# SSTuino_Evo.net
KiCad netlist of a schematic drawn in EAGLE
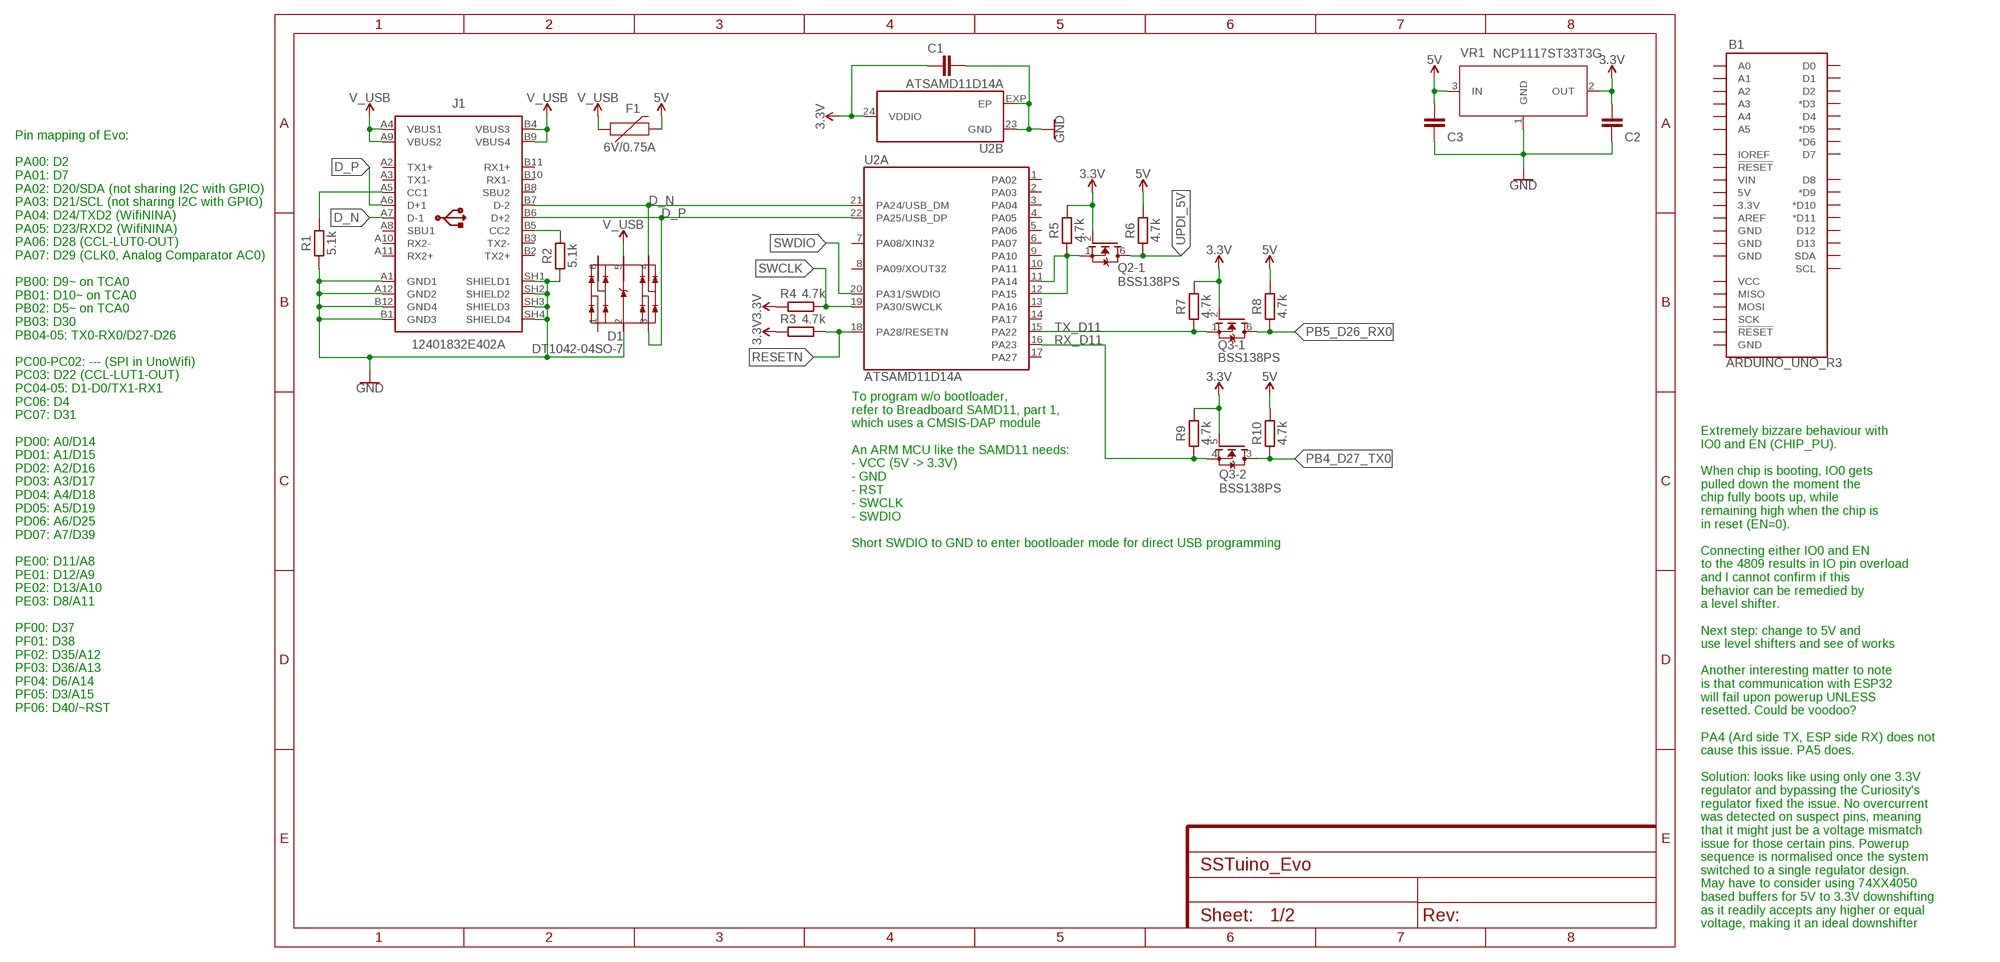
[diagram p0: schematic, sheet 1]
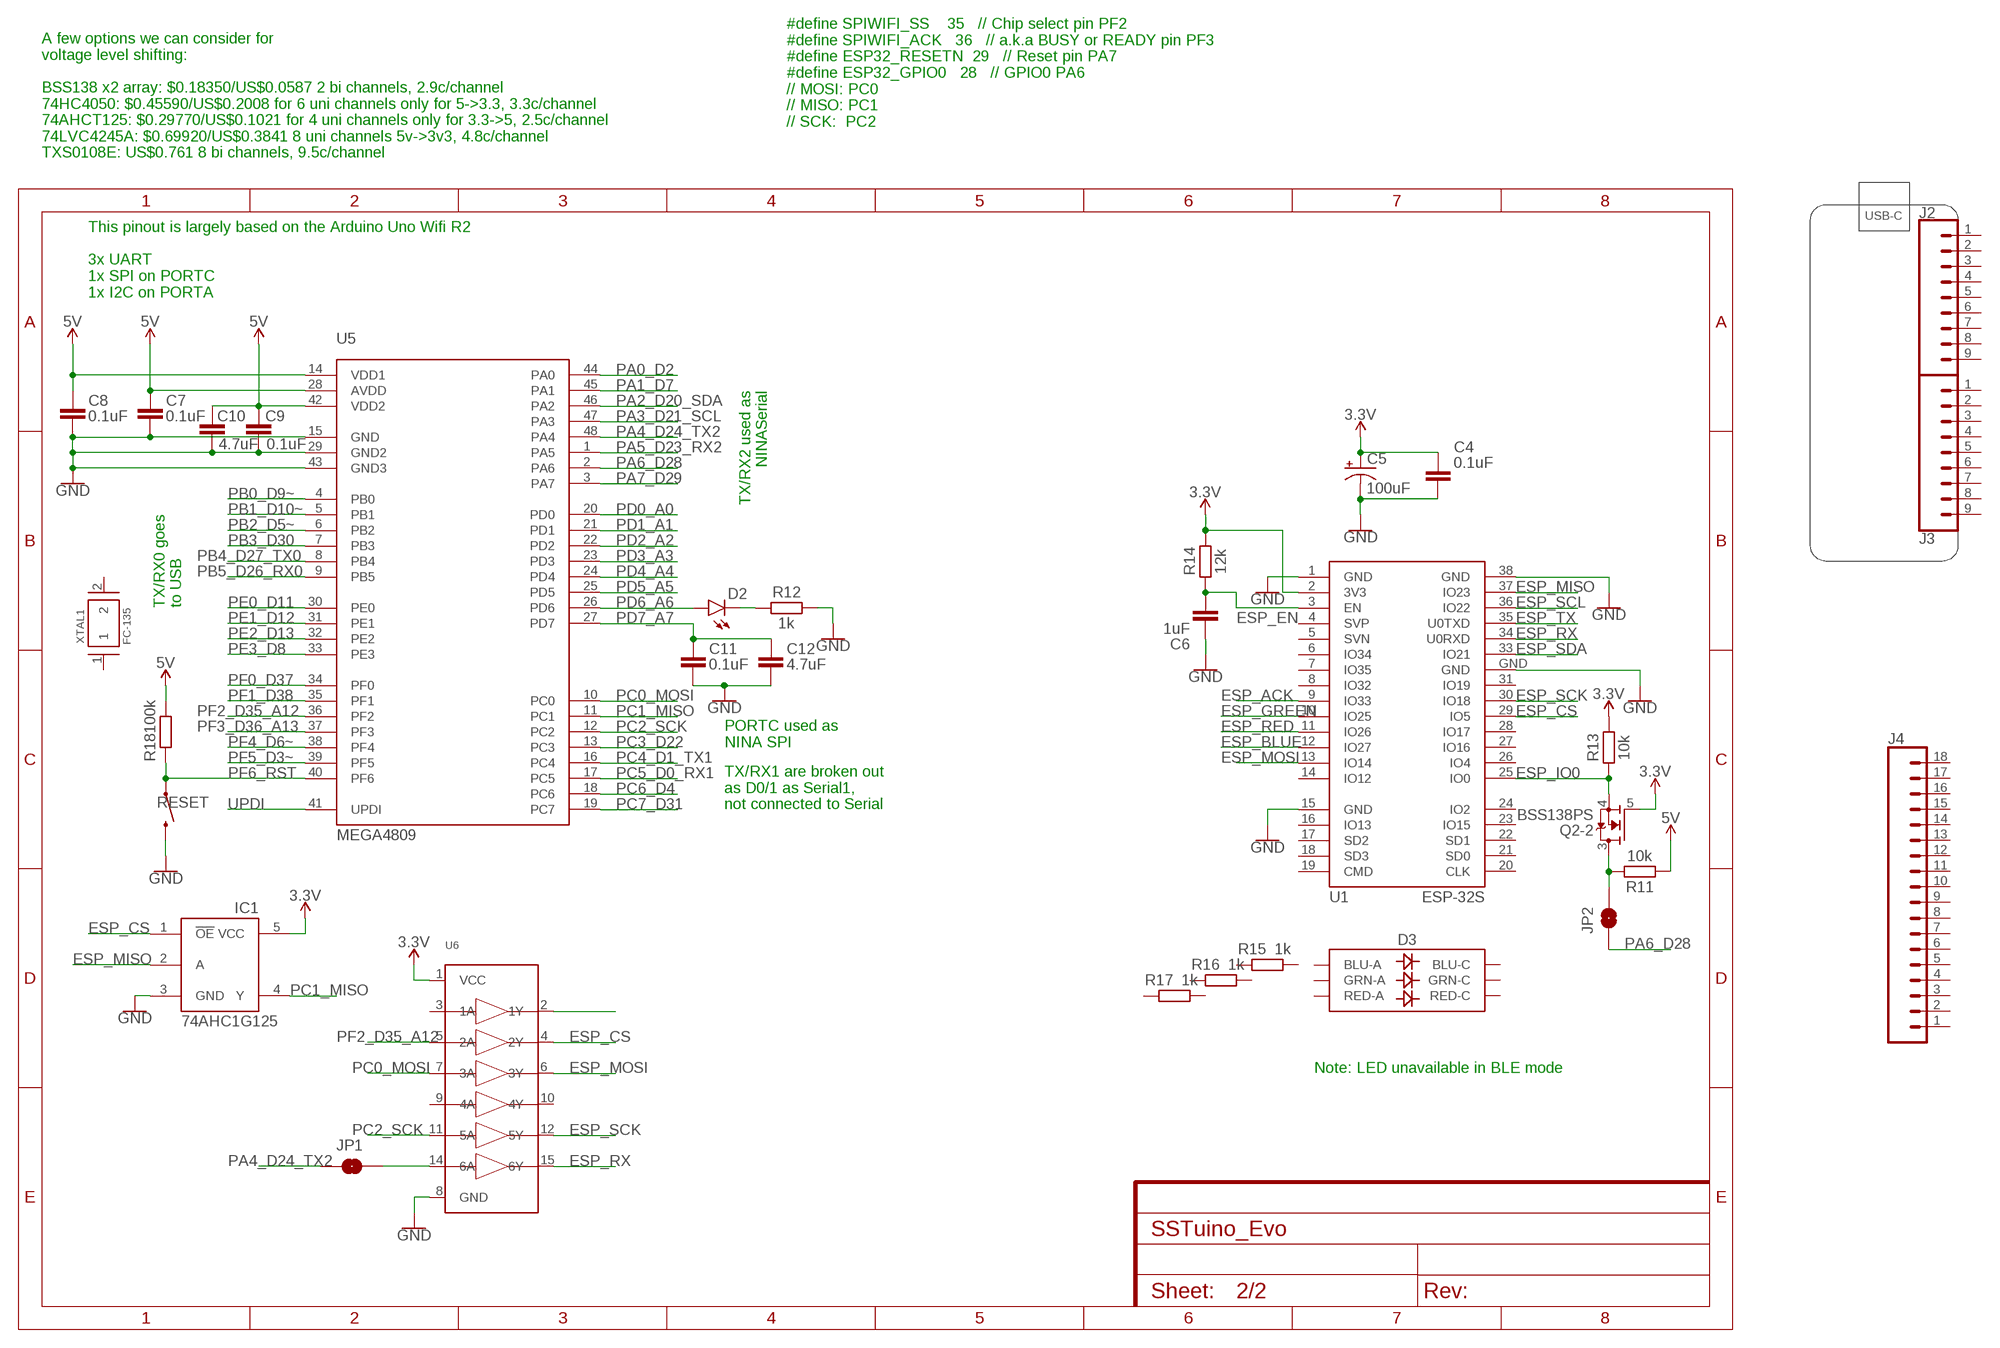
[diagram p1: schematic, sheet 2]

(export (version "E")
  (design (tool "Eeschema 10.0.6"))
  (components
    (comp (ref "B1")
      (value "ARDUINO_UNO_R3")
      (footprint "eagle-import:ARDUINO_R3")
      (libsource (lib "eagle-import") (part "ARDUINO_UNO_R3"))
    )
    (comp (ref "C1")
      (value "100n")
      (footprint "eagle-import:CAPC1005X60")
      (libsource (lib "eagle-import") (part "CCHIP-0402(1005-METRIC)_"))
    )
    (comp (ref "C2")
      (value "10uF")
      (footprint "eagle-import:CAPC1608X85")
      (libsource (lib "eagle-import") (part "CCHIP-0603(1608-METRIC)_"))
    )
    (comp (ref "C3")
      (value "10uF")
      (footprint "eagle-import:CAPC1608X85")
      (libsource (lib "eagle-import") (part "CCHIP-0603(1608-METRIC)_"))
    )
    (comp (ref "D1")
      (value "DT1042-04SO-7")
      (footprint "eagle-import:SOT95P285X140-6N")
      (fields (field (name "DIGI-KEY_PART_NUMBER") "DT1042-04SO-7DICT-ND") (field (name "MF") "Diodes Inc."))
      (libsource (lib "eagle-import") (part "DT1042-04SO-7"))
    )
    (comp (ref "F1")
      (value "6V/0.75A")
      (footprint "eagle-import:1206")
      (libsource (lib "eagle-import") (part "PPTC_THREE-QUARTER-AMP"))
    )
    (comp (ref "J1")
      (value "12401832E402A")
      (footprint "eagle-import:12401832E402A")
      (fields (field (name "MANUFACTURER") "Amphenol ICC"))
      (libsource (lib "eagle-import") (part "12401832E402A"))
    )
    (comp (ref "Q2")
      (value "BSS138PS")
      (footprint "eagle-import:ARDUINO-TRANSISTORS_SOT363")
      (fields (field (name "MANUFACTURER") "NXP"))
      (libsource (lib "eagle-import") (part "BSS138PS"))
    )
    (comp (ref "Q3")
      (value "BSS138PS")
      (footprint "eagle-import:ARDUINO-TRANSISTORS_SOT363")
      (fields (field (name "MANUFACTURER") "NXP"))
      (libsource (lib "eagle-import") (part "BSS138PS"))
    )
    (comp (ref "R1")
      (value "5.1k")
      (footprint "eagle-import:RESC1005X40")
      (libsource (lib "eagle-import") (part "RCHIP-0402(1005-METRIC)_"))
    )
    (comp (ref "R2")
      (value "5.1k")
      (footprint "eagle-import:RESC1005X40")
      (libsource (lib "eagle-import") (part "RCHIP-0402(1005-METRIC)_"))
    )
    (comp (ref "R3")
      (value "4.7k")
      (footprint "eagle-import:RESC1005X40")
      (libsource (lib "eagle-import") (part "RCHIP-0402(1005-METRIC)_"))
    )
    (comp (ref "R4")
      (value "4.7k")
      (footprint "eagle-import:RESC1005X40")
      (libsource (lib "eagle-import") (part "RCHIP-0402(1005-METRIC)_"))
    )
    (comp (ref "R5")
      (value "4.7k")
      (footprint "eagle-import:RESC1005X40")
      (libsource (lib "eagle-import") (part "RCHIP-0402(1005-METRIC)_"))
    )
    (comp (ref "R6")
      (value "4.7k")
      (footprint "eagle-import:RESC1005X40")
      (libsource (lib "eagle-import") (part "RCHIP-0402(1005-METRIC)_"))
    )
    (comp (ref "R7")
      (value "4.7k")
      (footprint "eagle-import:RESC1005X40")
      (libsource (lib "eagle-import") (part "RCHIP-0402(1005-METRIC)_"))
    )
    (comp (ref "R8")
      (value "4.7k")
      (footprint "eagle-import:RESC1005X40")
      (libsource (lib "eagle-import") (part "RCHIP-0402(1005-METRIC)_"))
    )
    (comp (ref "R9")
      (value "4.7k")
      (footprint "eagle-import:RESC1005X40")
      (libsource (lib "eagle-import") (part "RCHIP-0402(1005-METRIC)_"))
    )
    (comp (ref "R10")
      (value "4.7k")
      (footprint "eagle-import:RESC1005X40")
      (libsource (lib "eagle-import") (part "RCHIP-0402(1005-METRIC)_"))
    )
    (comp (ref "U2")
      (value "ATSAMD11D14A")
      (footprint "eagle-import:ARDUINO-UCS&SOCS_HVQFN24")
      (fields (field (name "MANUFACTURER") "Microchip"))
      (libsource (lib "eagle-import") (part "ATSAMD11D14"))
    )
    (comp (ref "VR1")
      (value "NCP1117ST33T3G")
      (footprint "eagle-import:SOT230P700X170-4")
      (fields (field (name "MANUFACTURER") "ON Semiconductor"))
      (libsource (lib "eagle-import") (part "NCP1117ST33T3GSOT-223"))
    )
    (comp (ref "C4")
      (value "0.1uF")
      (footprint "eagle-import:CAPC1005X60")
      (libsource (lib "eagle-import") (part "CCHIP-0402(1005-METRIC)_"))
    )
    (comp (ref "C5")
      (value "100uF")
      (footprint "eagle-import:CAPMP3216X180N")
      (libsource (lib "eagle-import") (part "C-POL-USTANTALUM-1206(3216-METRIC)_"))
    )
    (comp (ref "C6")
      (value "1uF")
      (footprint "eagle-import:CAPC1005X60")
      (libsource (lib "eagle-import") (part "CCHIP-0402(1005-METRIC)_"))
    )
    (comp (ref "C7")
      (value "0.1uF")
      (footprint "eagle-import:CAPC1005X60")
      (libsource (lib "eagle-import") (part "CCHIP-0402(1005-METRIC)_"))
    )
    (comp (ref "C8")
      (value "0.1uF")
      (footprint "eagle-import:CAPC1005X60")
      (libsource (lib "eagle-import") (part "CCHIP-0402(1005-METRIC)_"))
    )
    (comp (ref "C9")
      (value "0.1uF")
      (footprint "eagle-import:CAPC1005X60")
      (libsource (lib "eagle-import") (part "CCHIP-0402(1005-METRIC)_"))
    )
    (comp (ref "C10")
      (value "4.7uF")
      (footprint "eagle-import:CAPC1005X60")
      (libsource (lib "eagle-import") (part "CCHIP-0402(1005-METRIC)_"))
    )
    (comp (ref "C11")
      (value "0.1uF")
      (footprint "eagle-import:CAPC1005X60")
      (libsource (lib "eagle-import") (part "CCHIP-0402(1005-METRIC)_"))
    )
    (comp (ref "C12")
      (value "4.7uF")
      (footprint "eagle-import:CAPC1005X60")
      (libsource (lib "eagle-import") (part "CCHIP-0402(1005-METRIC)_"))
    )
    (comp (ref "D2")
      (value "LED0603")
      (footprint "eagle-import:LED-0603")
      (libsource (lib "eagle-import") (part "LED0603"))
    )
    (comp (ref "D3")
      (value "LED-RGBNO_IC")
      (footprint "eagle-import:LED-TRICOLOR-5050")
      (libsource (lib "eagle-import") (part "LED-RGBNO_IC"))
    )
    (comp (ref "IC1")
      (value "74AHC1G125")
      (footprint "eagle-import:SOT23-5L")
      (libsource (lib "eagle-import") (part "74AHC1G125"))
    )
    (comp (ref "J2")
      (value "CONN_09NO_SILK")
      (footprint "eagle-import:1X09_NO_SILK")
      (libsource (lib "eagle-import") (part "CONN_09NO_SILK"))
    )
    (comp (ref "J3")
      (value "CONN_09NO_SILK")
      (footprint "eagle-import:1X09_NO_SILK")
      (libsource (lib "eagle-import") (part "CONN_09NO_SILK"))
    )
    (comp (ref "J4")
      (value "CONN_18")
      (footprint "eagle-import:1X18")
      (libsource (lib "eagle-import") (part "CONN_18"))
    )
    (comp (ref "JP1")
      (value "JUMPER-SMT_2_NO_SILK")
      (footprint "eagle-import:SMT-JUMPER_2_NO_SILK")
      (libsource (lib "eagle-import") (part "JUMPER-SMT_2_NO_SILK"))
    )
    (comp (ref "JP2")
      (value "JUMPER-SMT_2_NO_SILK")
      (footprint "eagle-import:SMT-JUMPER_2_NO_SILK")
      (libsource (lib "eagle-import") (part "JUMPER-SMT_2_NO_SILK"))
    )
    (comp (ref "R11")
      (value "10k")
      (footprint "eagle-import:RESC1005X40")
      (libsource (lib "eagle-import") (part "RCHIP-0402(1005-METRIC)_"))
    )
    (comp (ref "R12")
      (value "1k")
      (footprint "eagle-import:RESC1005X40")
      (libsource (lib "eagle-import") (part "RCHIP-0402(1005-METRIC)_"))
    )
    (comp (ref "R13")
      (value "10k")
      (footprint "eagle-import:RESC1005X40")
      (libsource (lib "eagle-import") (part "RCHIP-0402(1005-METRIC)_"))
    )
    (comp (ref "R14")
      (value "12k")
      (footprint "eagle-import:RESC1005X40")
      (libsource (lib "eagle-import") (part "RCHIP-0402(1005-METRIC)_"))
    )
    (comp (ref "R15")
      (value "1k")
      (footprint "eagle-import:RESC1005X40")
      (libsource (lib "eagle-import") (part "RCHIP-0402(1005-METRIC)_"))
    )
    (comp (ref "R16")
      (value "1k")
      (footprint "eagle-import:RESC1005X40")
      (libsource (lib "eagle-import") (part "RCHIP-0402(1005-METRIC)_"))
    )
    (comp (ref "R17")
      (value "1k")
      (footprint "eagle-import:RESC1005X40")
      (libsource (lib "eagle-import") (part "RCHIP-0402(1005-METRIC)_"))
    )
    (comp (ref "R18")
      (value "100k")
      (footprint "eagle-import:RESC1005X40")
      (libsource (lib "eagle-import") (part "RCHIP-0402(1005-METRIC)_"))
    )
    (comp (ref "RESET")
      (value "MOMENTARY-SWITCH-SPST-SMD-4.6X2.8MM")
      (footprint "eagle-import:TACTILE_SWITCH_SMD_4.6X2.8MM")
      (libsource (lib "eagle-import") (part "MOMENTARY-SWITCH-SPST-SMD-4.6X2.8MM"))
    )
    (comp (ref "U1")
      (value "ESP-32S")
      (footprint "eagle-import:ESP-32S")
      (libsource (lib "eagle-import") (part "ESP-32S"))
    )
    (comp (ref "U5")
      (value "MEGA4809")
      (footprint "eagle-import:TQFP48")
      (libsource (lib "eagle-import") (part "MEGA4809"))
    )
    (comp (ref "U6")
      (value "74HC4050DTSSOP")
      (footprint "eagle-import:TSSOP16")
      (libsource (lib "eagle-import") (part "74HC4050DTSSOP"))
    )
    (comp (ref "XTAL1")
      (value "FC-135")
      (footprint "eagle-import:XTAL330X1051X90N")
      (fields (field (name "MANUFACTURER") "Seiko Epson Corporation"))
      (libsource (lib "eagle-import") (part "FC-135"))
    )
  )
  (nets
    (net (code "1") (name "3.3V") (class "Default")
      (node (ref "C1") (pin "1") (pinfunction "1_1") (pintype "passive"))
      (node (ref "C2") (pin "1") (pinfunction "1_1") (pintype "passive"))
      (node (ref "C4") (pin "1") (pinfunction "1_1") (pintype "passive"))
      (node (ref "C5") (pin "1") (pinfunction "+_1") (pintype "passive"))
      (node (ref "IC1") (pin "5") (pinfunction "VCC_5") (pintype "power_in"))
      (node (ref "Q2") (pin "2") (pinfunction "G_2") (pintype "passive"))
      (node (ref "Q2") (pin "5") (pinfunction "G_5") (pintype "passive"))
      (node (ref "Q3") (pin "2") (pinfunction "G_2") (pintype "passive"))
      (node (ref "Q3") (pin "5") (pinfunction "G_5") (pintype "passive"))
      (node (ref "R13") (pin "2") (pinfunction "2_2") (pintype "passive"))
      (node (ref "R14") (pin "2") (pinfunction "2_2") (pintype "passive"))
      (node (ref "R3") (pin "2") (pinfunction "2_2") (pintype "passive"))
      (node (ref "R4") (pin "2") (pinfunction "2_2") (pintype "passive"))
      (node (ref "R5") (pin "2") (pinfunction "2_2") (pintype "passive"))
      (node (ref "R7") (pin "2") (pinfunction "2_2") (pintype "passive"))
      (node (ref "R9") (pin "2") (pinfunction "2_2") (pintype "passive"))
      (node (ref "U1") (pin "2") (pinfunction "3V3_2") (pintype "power_in"))
      (node (ref "U2") (pin "24") (pinfunction "VDDIO_24") (pintype "power_in"))
      (node (ref "U6") (pin "1") (pinfunction "VCC_1") (pintype "bidirectional"))
      (node (ref "VR1") (pin "2") (pinfunction "OUT_2") (pintype "output"))
    )
    (net (code "2") (name "5V") (class "Default")
      (node (ref "C10") (pin "1") (pinfunction "1_1") (pintype "passive"))
      (node (ref "C3") (pin "1") (pinfunction "1_1") (pintype "passive"))
      (node (ref "C7") (pin "1") (pinfunction "1_1") (pintype "passive"))
      (node (ref "C8") (pin "1") (pinfunction "1_1") (pintype "passive"))
      (node (ref "C9") (pin "1") (pinfunction "1_1") (pintype "passive"))
      (node (ref "F1") (pin "2") (pinfunction "2_2") (pintype "bidirectional"))
      (node (ref "R10") (pin "2") (pinfunction "2_2") (pintype "passive"))
      (node (ref "R11") (pin "1") (pinfunction "1_1") (pintype "passive"))
      (node (ref "R18") (pin "2") (pinfunction "2_2") (pintype "passive"))
      (node (ref "R6") (pin "2") (pinfunction "2_2") (pintype "passive"))
      (node (ref "R8") (pin "2") (pinfunction "2_2") (pintype "passive"))
      (node (ref "U5") (pin "14") (pinfunction "VDD1_14") (pintype "bidirectional"))
      (node (ref "U5") (pin "28") (pinfunction "AVDD_28") (pintype "bidirectional"))
      (node (ref "U5") (pin "42") (pinfunction "VDD2_42") (pintype "bidirectional"))
      (node (ref "VR1") (pin "3") (pinfunction "IN_3") (pintype "input"))
    )
    (net (code "3") (name "D_N") (class "Default")
      (node (ref "D1") (pin "4") (pinfunction "IO3_4") (pintype "passive"))
      (node (ref "J1") (pin "A7") (pinfunction "D-1_A7") (pintype "bidirectional"))
      (node (ref "J1") (pin "B7") (pinfunction "D-2_B7") (pintype "bidirectional"))
      (node (ref "U2") (pin "21") (pinfunction "PA24/USB_DM_21") (pintype "bidirectional"))
    )
    (net (code "4") (name "D_P") (class "Default")
      (node (ref "D1") (pin "3") (pinfunction "IO2_3") (pintype "passive"))
      (node (ref "J1") (pin "A6") (pinfunction "D+1_A6") (pintype "bidirectional"))
      (node (ref "J1") (pin "B6") (pinfunction "D+2_B6") (pintype "bidirectional"))
      (node (ref "U2") (pin "22") (pinfunction "PA25/USB_DP_22") (pintype "bidirectional"))
    )
    (net (code "5") (name "ESP_ACK") (class "Default")
      (node (ref "U1") (pin "9") (pinfunction "IO33_9") (pintype "bidirectional"))
    )
    (net (code "6") (name "ESP_BLUE") (class "Default")
      (node (ref "U1") (pin "12") (pinfunction "IO27_12") (pintype "bidirectional"))
    )
    (net (code "7") (name "ESP_CS") (class "Default")
      (node (ref "IC1") (pin "1") (pinfunction "~{OE}_1") (pintype "input"))
      (node (ref "U1") (pin "29") (pinfunction "IO5_29") (pintype "bidirectional"))
      (node (ref "U6") (pin "4") (pinfunction "2Y_4") (pintype "bidirectional"))
    )
    (net (code "8") (name "ESP_EN") (class "Default")
      (node (ref "C6") (pin "2") (pinfunction "2_2") (pintype "passive"))
      (node (ref "R14") (pin "1") (pinfunction "1_1") (pintype "passive"))
      (node (ref "U1") (pin "3") (pinfunction "EN_3") (pintype "input"))
    )
    (net (code "9") (name "ESP_GREEN") (class "Default")
      (node (ref "U1") (pin "10") (pinfunction "IO25_10") (pintype "bidirectional"))
    )
    (net (code "10") (name "ESP_IO0") (class "Default")
      (node (ref "Q2") (pin "4") (pinfunction "S_4") (pintype "passive"))
      (node (ref "R13") (pin "1") (pinfunction "1_1") (pintype "passive"))
      (node (ref "U1") (pin "25") (pinfunction "IO0_25") (pintype "bidirectional"))
    )
    (net (code "11") (name "ESP_MISO") (class "Default")
      (node (ref "IC1") (pin "2") (pinfunction "A_2") (pintype "input"))
      (node (ref "U1") (pin "37") (pinfunction "IO23_37") (pintype "bidirectional"))
    )
    (net (code "12") (name "ESP_MOSI") (class "Default")
      (node (ref "U1") (pin "13") (pinfunction "IO14_13") (pintype "bidirectional"))
      (node (ref "U6") (pin "6") (pinfunction "3Y_6") (pintype "bidirectional"))
    )
    (net (code "13") (name "ESP_RED") (class "Default")
      (node (ref "U1") (pin "11") (pinfunction "IO26_11") (pintype "bidirectional"))
    )
    (net (code "14") (name "ESP_RX") (class "Default")
      (node (ref "U1") (pin "34") (pinfunction "U0RXD_34") (pintype "bidirectional"))
      (node (ref "U6") (pin "15") (pinfunction "6Y_15") (pintype "bidirectional"))
    )
    (net (code "15") (name "ESP_SCK") (class "Default")
      (node (ref "U1") (pin "30") (pinfunction "IO18_30") (pintype "bidirectional"))
      (node (ref "U6") (pin "12") (pinfunction "5Y_12") (pintype "bidirectional"))
    )
    (net (code "16") (name "ESP_SCL") (class "Default")
      (node (ref "U1") (pin "36") (pinfunction "IO22_36") (pintype "bidirectional"))
    )
    (net (code "17") (name "ESP_SDA") (class "Default")
      (node (ref "U1") (pin "33") (pinfunction "IO21_33") (pintype "bidirectional"))
    )
    (net (code "18") (name "ESP_TX") (class "Default")
      (node (ref "U1") (pin "35") (pinfunction "U0TXD_35") (pintype "bidirectional"))
    )
    (net (code "19") (name "GND") (class "Default")
      (node (ref "C1") (pin "2") (pinfunction "2_2") (pintype "passive"))
      (node (ref "C10") (pin "2") (pinfunction "2_2") (pintype "passive"))
      (node (ref "C11") (pin "2") (pinfunction "2_2") (pintype "passive"))
      (node (ref "C12") (pin "2") (pinfunction "2_2") (pintype "passive"))
      (node (ref "C2") (pin "2") (pinfunction "2_2") (pintype "passive"))
      (node (ref "C3") (pin "2") (pinfunction "2_2") (pintype "passive"))
      (node (ref "C4") (pin "2") (pinfunction "2_2") (pintype "passive"))
      (node (ref "C5") (pin "2") (pinfunction "-_2") (pintype "passive"))
      (node (ref "C6") (pin "1") (pinfunction "1_1") (pintype "passive"))
      (node (ref "C7") (pin "2") (pinfunction "2_2") (pintype "passive"))
      (node (ref "C8") (pin "2") (pinfunction "2_2") (pintype "passive"))
      (node (ref "C9") (pin "2") (pinfunction "2_2") (pintype "passive"))
      (node (ref "D1") (pin "2") (pinfunction "VSS_2") (pintype "power_in"))
      (node (ref "IC1") (pin "3") (pinfunction "GND_3") (pintype "power_in"))
      (node (ref "J1") (pin "A1") (pinfunction "GND1_A1") (pintype "power_in"))
      (node (ref "J1") (pin "A12") (pinfunction "GND2_A12") (pintype "power_in"))
      (node (ref "J1") (pin "B1") (pinfunction "GND3_B1") (pintype "power_in"))
      (node (ref "J1") (pin "B12") (pinfunction "GND4_B12") (pintype "power_in"))
      (node (ref "J1") (pin "SH1") (pinfunction "SHIELD1_SH1") (pintype "power_in"))
      (node (ref "J1") (pin "SH2") (pinfunction "SHIELD2_SH2") (pintype "power_in"))
      (node (ref "J1") (pin "SH3") (pinfunction "SHIELD3_SH3") (pintype "power_in"))
      (node (ref "J1") (pin "SH4") (pinfunction "SHIELD4_SH4") (pintype "power_in"))
      (node (ref "R1") (pin "1") (pinfunction "1_1") (pintype "passive"))
      (node (ref "R12") (pin "2") (pinfunction "2_2") (pintype "passive"))
      (node (ref "R2") (pin "1") (pinfunction "1_1") (pintype "passive"))
      (node (ref "RESET") (pin "3") (pinfunction "2_3") (pintype "passive"))
      (node (ref "RESET") (pin "4") (pinfunction "2_4") (pintype "passive"))
      (node (ref "U1") (pin "1") (pinfunction "GND_1") (pintype "power_in"))
      (node (ref "U1") (pin "15") (pinfunction "GND_15") (pintype "power_in"))
      (node (ref "U1") (pin "38") (pinfunction "GND_38") (pintype "power_in"))
      (node (ref "U1") (pin "GND") (pinfunction "GND_GND") (pintype "power_in"))
      (node (ref "U2") (pin "23") (pinfunction "GND_23") (pintype "power_in"))
      (node (ref "U2") (pin "EXP") (pinfunction "EP_EXP") (pintype "power_in"))
      (node (ref "U5") (pin "15") (pinfunction "GND_15") (pintype "bidirectional"))
      (node (ref "U5") (pin "29") (pinfunction "GND2_29") (pintype "bidirectional"))
      (node (ref "U5") (pin "43") (pinfunction "GND3_43") (pintype "bidirectional"))
      (node (ref "U6") (pin "8") (pinfunction "GND_8") (pintype "bidirectional"))
      (node (ref "VR1") (pin "1") (pinfunction "GND_1") (pintype "passive"))
    )
    (net (code "20") (name "Net-(D2-PadC)") (class "Default")
      (node (ref "D2") (pin "C") (pinfunction "C_C") (pintype "passive"))
      (node (ref "R12") (pin "1") (pinfunction "1_1") (pintype "passive"))
    )
    (net (code "21") (name "Net-(J1-CC1)") (class "Default")
      (node (ref "J1") (pin "A5") (pinfunction "CC1_A5") (pintype "bidirectional"))
      (node (ref "R1") (pin "2") (pinfunction "2_2") (pintype "passive"))
    )
    (net (code "22") (name "Net-(J1-CC2)") (class "Default")
      (node (ref "J1") (pin "B5") (pinfunction "CC2_B5") (pintype "bidirectional"))
      (node (ref "R2") (pin "2") (pinfunction "2_2") (pintype "passive"))
    )
    (net (code "23") (name "Net-(Q2A-S)") (class "Default")
      (node (ref "Q2") (pin "1") (pinfunction "S_1") (pintype "passive"))
      (node (ref "R5") (pin "1") (pinfunction "1_1") (pintype "passive"))
      (node (ref "U2") (pin "11") (pinfunction "PA14_11") (pintype "bidirectional"))
      (node (ref "U2") (pin "12") (pinfunction "PA15_12") (pintype "bidirectional"))
    )
    (net (code "24") (name "Net-(Q2B-D)") (class "Default")
      (node (ref "JP2") (pin "2") (pinfunction "2_2") (pintype "passive"))
      (node (ref "Q2") (pin "3") (pinfunction "D_3") (pintype "passive"))
      (node (ref "R11") (pin "2") (pinfunction "2_2") (pintype "passive"))
    )
    (net (code "25") (name "Net-(U6-6A)") (class "Default")
      (node (ref "JP1") (pin "2") (pinfunction "2_2") (pintype "passive"))
      (node (ref "U6") (pin "14") (pinfunction "6A_14") (pintype "bidirectional"))
    )
    (net (code "26") (name "PA0_D2") (class "Default")
      (node (ref "U5") (pin "44") (pinfunction "PA0_44") (pintype "bidirectional"))
    )
    (net (code "27") (name "PA1_D7") (class "Default")
      (node (ref "U5") (pin "45") (pinfunction "PA1_45") (pintype "bidirectional"))
    )
    (net (code "28") (name "PA2_D20_SDA") (class "Default")
      (node (ref "U5") (pin "46") (pinfunction "PA2_46") (pintype "bidirectional"))
    )
    (net (code "29") (name "PA3_D21_SCL") (class "Default")
      (node (ref "U5") (pin "47") (pinfunction "PA3_47") (pintype "bidirectional"))
    )
    (net (code "30") (name "PA4_D24_TX2") (class "Default")
      (node (ref "JP1") (pin "1") (pinfunction "1_1") (pintype "passive"))
      (node (ref "U5") (pin "48") (pinfunction "PA4_48") (pintype "bidirectional"))
    )
    (net (code "31") (name "PA5_D23_RX2") (class "Default")
      (node (ref "U5") (pin "1") (pinfunction "PA5_1") (pintype "bidirectional"))
    )
    (net (code "32") (name "PA6_D28") (class "Default")
      (node (ref "JP2") (pin "1") (pinfunction "1_1") (pintype "passive"))
      (node (ref "U5") (pin "2") (pinfunction "PA6_2") (pintype "bidirectional"))
    )
    (net (code "33") (name "PA7_D29") (class "Default")
      (node (ref "U5") (pin "3") (pinfunction "PA7_3") (pintype "bidirectional"))
    )
    (net (code "34") (name "PB0_D9~{}") (class "Default")
      (node (ref "U5") (pin "4") (pinfunction "PB0_4") (pintype "bidirectional"))
    )
    (net (code "35") (name "PB1_D10~{}") (class "Default")
      (node (ref "U5") (pin "5") (pinfunction "PB1_5") (pintype "bidirectional"))
    )
    (net (code "36") (name "PB2_D5~{}") (class "Default")
      (node (ref "U5") (pin "6") (pinfunction "PB2_6") (pintype "bidirectional"))
    )
    (net (code "37") (name "PB3_D30") (class "Default")
      (node (ref "U5") (pin "7") (pinfunction "PB3_7") (pintype "bidirectional"))
    )
    (net (code "38") (name "PB4_D27_TX0") (class "Default")
      (node (ref "Q3") (pin "3") (pinfunction "D_3") (pintype "passive"))
      (node (ref "R10") (pin "1") (pinfunction "1_1") (pintype "passive"))
      (node (ref "U5") (pin "8") (pinfunction "PB4_8") (pintype "bidirectional"))
    )
    (net (code "39") (name "PB5_D26_RX0") (class "Default")
      (node (ref "Q3") (pin "6") (pinfunction "D_6") (pintype "passive"))
      (node (ref "R8") (pin "1") (pinfunction "1_1") (pintype "passive"))
      (node (ref "U5") (pin "9") (pinfunction "PB5_9") (pintype "bidirectional"))
    )
    (net (code "40") (name "PC0_MOSI") (class "Default")
      (node (ref "U5") (pin "10") (pinfunction "PC0_10") (pintype "bidirectional"))
      (node (ref "U6") (pin "7") (pinfunction "3A_7") (pintype "bidirectional"))
    )
    (net (code "41") (name "PC1_MISO") (class "Default")
      (node (ref "IC1") (pin "4") (pinfunction "Y_4") (pintype "output"))
      (node (ref "U5") (pin "11") (pinfunction "PC1_11") (pintype "bidirectional"))
    )
    (net (code "42") (name "PC2_SCK") (class "Default")
      (node (ref "U5") (pin "12") (pinfunction "PC2_12") (pintype "bidirectional"))
      (node (ref "U6") (pin "11") (pinfunction "5A_11") (pintype "bidirectional"))
    )
    (net (code "43") (name "PC3_D22") (class "Default")
      (node (ref "U5") (pin "13") (pinfunction "PC3_13") (pintype "bidirectional"))
    )
    (net (code "44") (name "PC4_D1_TX1") (class "Default")
      (node (ref "U5") (pin "16") (pinfunction "PC4_16") (pintype "bidirectional"))
    )
    (net (code "45") (name "PC5_D0_RX1") (class "Default")
      (node (ref "U5") (pin "17") (pinfunction "PC5_17") (pintype "bidirectional"))
    )
    (net (code "46") (name "PC6_D4") (class "Default")
      (node (ref "U5") (pin "18") (pinfunction "PC6_18") (pintype "bidirectional"))
    )
    (net (code "47") (name "PC7_D31") (class "Default")
      (node (ref "U5") (pin "19") (pinfunction "PC7_19") (pintype "bidirectional"))
    )
    (net (code "48") (name "PD0_A0") (class "Default")
      (node (ref "U5") (pin "20") (pinfunction "PD0_20") (pintype "bidirectional"))
    )
    (net (code "49") (name "PD1_A1") (class "Default")
      (node (ref "U5") (pin "21") (pinfunction "PD1_21") (pintype "bidirectional"))
    )
    (net (code "50") (name "PD2_A2") (class "Default")
      (node (ref "U5") (pin "22") (pinfunction "PD2_22") (pintype "bidirectional"))
    )
    (net (code "51") (name "PD3_A3") (class "Default")
      (node (ref "U5") (pin "23") (pinfunction "PD3_23") (pintype "bidirectional"))
    )
    (net (code "52") (name "PD4_A4") (class "Default")
      (node (ref "U5") (pin "24") (pinfunction "PD4_24") (pintype "bidirectional"))
    )
    (net (code "53") (name "PD5_A5") (class "Default")
      (node (ref "U5") (pin "25") (pinfunction "PD5_25") (pintype "bidirectional"))
    )
    (net (code "54") (name "PD6_A6") (class "Default")
      (node (ref "D2") (pin "A") (pinfunction "A_A") (pintype "passive"))
      (node (ref "U5") (pin "26") (pinfunction "PD6_26") (pintype "bidirectional"))
    )
    (net (code "55") (name "PD7_A7") (class "Default")
      (node (ref "C11") (pin "1") (pinfunction "1_1") (pintype "passive"))
      (node (ref "C12") (pin "1") (pinfunction "1_1") (pintype "passive"))
      (node (ref "U5") (pin "27") (pinfunction "PD7_27") (pintype "bidirectional"))
    )
    (net (code "56") (name "PE0_D11") (class "Default")
      (node (ref "U5") (pin "30") (pinfunction "PE0_30") (pintype "bidirectional"))
    )
    (net (code "57") (name "PE1_D12") (class "Default")
      (node (ref "U5") (pin "31") (pinfunction "PE1_31") (pintype "bidirectional"))
    )
    (net (code "58") (name "PE2_D13") (class "Default")
      (node (ref "U5") (pin "32") (pinfunction "PE2_32") (pintype "bidirectional"))
    )
    (net (code "59") (name "PE3_D8") (class "Default")
      (node (ref "U5") (pin "33") (pinfunction "PE3_33") (pintype "bidirectional"))
    )
    (net (code "60") (name "PF0_D37") (class "Default")
      (node (ref "U5") (pin "34") (pinfunction "PF0_34") (pintype "bidirectional"))
    )
    (net (code "61") (name "PF1_D38") (class "Default")
      (node (ref "U5") (pin "35") (pinfunction "PF1_35") (pintype "bidirectional"))
    )
    (net (code "62") (name "PF2_D35_A12") (class "Default")
      (node (ref "U5") (pin "36") (pinfunction "PF2_36") (pintype "bidirectional"))
      (node (ref "U6") (pin "5") (pinfunction "2A_5") (pintype "bidirectional"))
    )
    (net (code "63") (name "PF3_D36_A13") (class "Default")
      (node (ref "U5") (pin "37") (pinfunction "PF3_37") (pintype "bidirectional"))
    )
    (net (code "64") (name "PF4_D6~{}") (class "Default")
      (node (ref "U5") (pin "38") (pinfunction "PF4_38") (pintype "bidirectional"))
    )
    (net (code "65") (name "PF5_D3~{}") (class "Default")
      (node (ref "U5") (pin "39") (pinfunction "PF5_39") (pintype "bidirectional"))
    )
    (net (code "66") (name "PF6_RST") (class "Default")
      (node (ref "R18") (pin "1") (pinfunction "1_1") (pintype "passive"))
      (node (ref "RESET") (pin "1") (pinfunction "1_1") (pintype "passive"))
      (node (ref "RESET") (pin "2") (pinfunction "1_2") (pintype "passive"))
      (node (ref "U5") (pin "40") (pinfunction "PF6_40") (pintype "bidirectional"))
    )
    (net (code "67") (name "RESETN") (class "Default")
      (node (ref "R3") (pin "1") (pinfunction "1_1") (pintype "passive"))
      (node (ref "U2") (pin "18") (pinfunction "PA28/RESETN_18") (pintype "bidirectional"))
    )
    (net (code "68") (name "RX_D11") (class "Default")
      (node (ref "Q3") (pin "4") (pinfunction "S_4") (pintype "passive"))
      (node (ref "R9") (pin "1") (pinfunction "1_1") (pintype "passive"))
      (node (ref "U2") (pin "16") (pinfunction "PA23_16") (pintype "bidirectional"))
    )
    (net (code "69") (name "SWCLK") (class "Default")
      (node (ref "R4") (pin "1") (pinfunction "1_1") (pintype "passive"))
      (node (ref "U2") (pin "19") (pinfunction "PA30/SWCLK_19") (pintype "bidirectional"))
    )
    (net (code "70") (name "SWDIO") (class "Default")
      (node (ref "U2") (pin "20") (pinfunction "PA31/SWDIO_20") (pintype "bidirectional"))
    )
    (net (code "71") (name "TX_D11") (class "Default")
      (node (ref "Q3") (pin "1") (pinfunction "S_1") (pintype "passive"))
      (node (ref "R7") (pin "1") (pinfunction "1_1") (pintype "passive"))
      (node (ref "U2") (pin "15") (pinfunction "PA22_15") (pintype "bidirectional"))
    )
    (net (code "72") (name "UPDI") (class "Default")
      (node (ref "U5") (pin "41") (pinfunction "UPDI_41") (pintype "bidirectional"))
    )
    (net (code "73") (name "UPDI_5V") (class "Default")
      (node (ref "Q2") (pin "6") (pinfunction "D_6") (pintype "passive"))
      (node (ref "R6") (pin "1") (pinfunction "1_1") (pintype "passive"))
    )
    (net (code "74") (name "V_USB") (class "Default")
      (node (ref "D1") (pin "5") (pinfunction "VCC_5") (pintype "power_in"))
      (node (ref "F1") (pin "1") (pinfunction "1_1") (pintype "bidirectional"))
      (node (ref "J1") (pin "A4") (pinfunction "VBUS1_A4") (pintype "power_in"))
      (node (ref "J1") (pin "A9") (pinfunction "VBUS2_A9") (pintype "power_in"))
      (node (ref "J1") (pin "B4") (pinfunction "VBUS3_B4") (pintype "power_in"))
      (node (ref "J1") (pin "B9") (pinfunction "VBUS4_B9") (pintype "power_in"))
    )
    (net (code "75") (name "unconnected-(B1-*D3-PadD3)") (class "Default")
      (node (ref "B1") (pin "D3") (pinfunction "*D3_D3") (pintype "bidirectional"))
    )
    (net (code "76") (name "unconnected-(B1-*D5-PadD5)") (class "Default")
      (node (ref "B1") (pin "D5") (pinfunction "*D5_D5") (pintype "bidirectional"))
    )
    (net (code "77") (name "unconnected-(B1-*D6-PadD6)") (class "Default")
      (node (ref "B1") (pin "D6") (pinfunction "*D6_D6") (pintype "bidirectional"))
    )
    (net (code "78") (name "unconnected-(B1-*D9-PadD9)") (class "Default")
      (node (ref "B1") (pin "D9") (pinfunction "*D9_D9") (pintype "bidirectional"))
    )
    (net (code "79") (name "unconnected-(B1-*D10-PadD10)") (class "Default")
      (node (ref "B1") (pin "D10") (pinfunction "*D10_D10") (pintype "bidirectional"))
    )
    (net (code "80") (name "unconnected-(B1-*D11-PadD11)") (class "Default")
      (node (ref "B1") (pin "D11") (pinfunction "*D11_D11") (pintype "bidirectional"))
    )
    (net (code "81") (name "unconnected-(B1-GND-PadGND@1)") (class "Default")
      (node (ref "B1") (pin "GND@1") (pinfunction "GND_GND@1") (pintype "bidirectional"))
    )
    (net (code "82") (name "unconnected-(B1-GND-PadGND@2)") (class "Default")
      (node (ref "B1") (pin "GND@2") (pinfunction "GND_GND@2") (pintype "bidirectional"))
    )
    (net (code "83") (name "unconnected-(B1-GND-PadGND@3)") (class "Default")
      (node (ref "B1") (pin "GND@3") (pinfunction "GND_GND@3") (pintype "bidirectional"))
    )
    (net (code "84") (name "unconnected-(B1-GND-PadGND@4)") (class "Default")
      (node (ref "B1") (pin "GND@4") (pinfunction "GND_GND@4") (pintype "bidirectional"))
    )
    (net (code "85") (name "unconnected-(B1-Pad3.3V)") (class "Default")
      (node (ref "B1") (pin "3.3V") (pinfunction "3.3V_3.3V") (pintype "bidirectional"))
    )
    (net (code "86") (name "unconnected-(B1-Pad5V)") (class "Default")
      (node (ref "B1") (pin "5V") (pinfunction "5V_5V") (pintype "bidirectional"))
    )
    (net (code "87") (name "unconnected-(B1-PadA0)") (class "Default")
      (node (ref "B1") (pin "A0") (pinfunction "A0_A0") (pintype "bidirectional"))
    )
    (net (code "88") (name "unconnected-(B1-PadA1)") (class "Default")
      (node (ref "B1") (pin "A1") (pinfunction "A1_A1") (pintype "bidirectional"))
    )
    (net (code "89") (name "unconnected-(B1-PadA2)") (class "Default")
      (node (ref "B1") (pin "A2") (pinfunction "A2_A2") (pintype "bidirectional"))
    )
    (net (code "90") (name "unconnected-(B1-PadA3)") (class "Default")
      (node (ref "B1") (pin "A3") (pinfunction "A3_A3") (pintype "bidirectional"))
    )
    (net (code "91") (name "unconnected-(B1-PadA4)") (class "Default")
      (node (ref "B1") (pin "A4") (pinfunction "A4_A4") (pintype "bidirectional"))
    )
    (net (code "92") (name "unconnected-(B1-PadA5)") (class "Default")
      (node (ref "B1") (pin "A5") (pinfunction "A5_A5") (pintype "bidirectional"))
    )
    (net (code "93") (name "unconnected-(B1-PadAREF)") (class "Default")
      (node (ref "B1") (pin "AREF") (pinfunction "AREF_AREF") (pintype "bidirectional"))
    )
    (net (code "94") (name "unconnected-(B1-PadD0)") (class "Default")
      (node (ref "B1") (pin "D0") (pinfunction "D0_D0") (pintype "bidirectional"))
    )
    (net (code "95") (name "unconnected-(B1-PadD1)") (class "Default")
      (node (ref "B1") (pin "D1") (pinfunction "D1_D1") (pintype "bidirectional"))
    )
    (net (code "96") (name "unconnected-(B1-PadD2)") (class "Default")
      (node (ref "B1") (pin "D2") (pinfunction "D2_D2") (pintype "bidirectional"))
    )
    (net (code "97") (name "unconnected-(B1-PadD4)") (class "Default")
      (node (ref "B1") (pin "D4") (pinfunction "D4_D4") (pintype "bidirectional"))
    )
    (net (code "98") (name "unconnected-(B1-PadD7)") (class "Default")
      (node (ref "B1") (pin "D7") (pinfunction "D7_D7") (pintype "bidirectional"))
    )
    (net (code "99") (name "unconnected-(B1-PadD8)") (class "Default")
      (node (ref "B1") (pin "D8") (pinfunction "D8_D8") (pintype "bidirectional"))
    )
    (net (code "100") (name "unconnected-(B1-PadD12)") (class "Default")
      (node (ref "B1") (pin "D12") (pinfunction "D12_D12") (pintype "bidirectional"))
    )
    (net (code "101") (name "unconnected-(B1-PadD13)") (class "Default")
      (node (ref "B1") (pin "D13") (pinfunction "D13_D13") (pintype "bidirectional"))
    )
    (net (code "102") (name "unconnected-(B1-PadIOREF)") (class "Default")
      (node (ref "B1") (pin "IOREF") (pinfunction "IOREF_IOREF") (pintype "bidirectional"))
    )
    (net (code "103") (name "unconnected-(B1-PadMISO)") (class "Default")
      (node (ref "B1") (pin "MISO") (pinfunction "MISO_MISO") (pintype "bidirectional"))
    )
    (net (code "104") (name "unconnected-(B1-PadMOSI)") (class "Default")
      (node (ref "B1") (pin "MOSI") (pinfunction "MOSI_MOSI") (pintype "bidirectional"))
    )
    (net (code "105") (name "unconnected-(B1-PadSCK)") (class "Default")
      (node (ref "B1") (pin "SCK") (pinfunction "SCK_SCK") (pintype "bidirectional"))
    )
    (net (code "106") (name "unconnected-(B1-PadSCL)") (class "Default")
      (node (ref "B1") (pin "SCL") (pinfunction "SCL_SCL") (pintype "bidirectional"))
    )
    (net (code "107") (name "unconnected-(B1-PadSDA)") (class "Default")
      (node (ref "B1") (pin "SDA") (pinfunction "SDA_SDA") (pintype "bidirectional"))
    )
    (net (code "108") (name "unconnected-(B1-PadVCC)") (class "Default")
      (node (ref "B1") (pin "VCC") (pinfunction "VCC_VCC") (pintype "bidirectional"))
    )
    (net (code "109") (name "unconnected-(B1-PadVIN)") (class "Default")
      (node (ref "B1") (pin "VIN") (pinfunction "VIN_VIN") (pintype "bidirectional"))
    )
    (net (code "110") (name "unconnected-(B1-~{RESET}-PadRESET@1)") (class "Default")
      (node (ref "B1") (pin "RESET@1") (pinfunction "~{RESET}_RESET@1") (pintype "bidirectional"))
    )
    (net (code "111") (name "unconnected-(B1-~{RESET}-PadRESET@2)") (class "Default")
      (node (ref "B1") (pin "RESET@2") (pinfunction "~{RESET}_RESET@2") (pintype "bidirectional"))
    )
    (net (code "112") (name "unconnected-(D1-IO1-Pad1)") (class "Default")
      (node (ref "D1") (pin "1") (pinfunction "IO1_1") (pintype "passive"))
    )
    (net (code "113") (name "unconnected-(D1-IO4-Pad6)") (class "Default")
      (node (ref "D1") (pin "6") (pinfunction "IO4_6") (pintype "passive"))
    )
    (net (code "114") (name "unconnected-(D3-BLU-A-Pad3)") (class "Default")
      (node (ref "D3") (pin "3") (pinfunction "BLU-A_3") (pintype "bidirectional"))
    )
    (net (code "115") (name "unconnected-(D3-BLU-C-Pad4)") (class "Default")
      (node (ref "D3") (pin "4") (pinfunction "BLU-C_4") (pintype "bidirectional"))
    )
    (net (code "116") (name "unconnected-(D3-GRN-A-Pad1)") (class "Default")
      (node (ref "D3") (pin "1") (pinfunction "GRN-A_1") (pintype "bidirectional"))
    )
    (net (code "117") (name "unconnected-(D3-GRN-C-Pad6)") (class "Default")
      (node (ref "D3") (pin "6") (pinfunction "GRN-C_6") (pintype "bidirectional"))
    )
    (net (code "118") (name "unconnected-(D3-RED-A-Pad2)") (class "Default")
      (node (ref "D3") (pin "2") (pinfunction "RED-A_2") (pintype "bidirectional"))
    )
    (net (code "119") (name "unconnected-(D3-RED-C-Pad5)") (class "Default")
      (node (ref "D3") (pin "5") (pinfunction "RED-C_5") (pintype "bidirectional"))
    )
    (net (code "120") (name "unconnected-(J1-RX1+-PadB11)") (class "Default")
      (node (ref "J1") (pin "B11") (pinfunction "RX1+_B11") (pintype "bidirectional"))
    )
    (net (code "121") (name "unconnected-(J1-RX1--PadB10)") (class "Default")
      (node (ref "J1") (pin "B10") (pinfunction "RX1-_B10") (pintype "bidirectional"))
    )
    (net (code "122") (name "unconnected-(J1-RX2+-PadA11)") (class "Default")
      (node (ref "J1") (pin "A11") (pinfunction "RX2+_A11") (pintype "bidirectional"))
    )
    (net (code "123") (name "unconnected-(J1-RX2--PadA10)") (class "Default")
      (node (ref "J1") (pin "A10") (pinfunction "RX2-_A10") (pintype "bidirectional"))
    )
    (net (code "124") (name "unconnected-(J1-SBU1-PadA8)") (class "Default")
      (node (ref "J1") (pin "A8") (pinfunction "SBU1_A8") (pintype "bidirectional"))
    )
    (net (code "125") (name "unconnected-(J1-SBU2-PadB8)") (class "Default")
      (node (ref "J1") (pin "B8") (pinfunction "SBU2_B8") (pintype "bidirectional"))
    )
    (net (code "126") (name "unconnected-(J1-TX1+-PadA2)") (class "Default")
      (node (ref "J1") (pin "A2") (pinfunction "TX1+_A2") (pintype "bidirectional"))
    )
    (net (code "127") (name "unconnected-(J1-TX1--PadA3)") (class "Default")
      (node (ref "J1") (pin "A3") (pinfunction "TX1-_A3") (pintype "bidirectional"))
    )
    (net (code "128") (name "unconnected-(J1-TX2+-PadB2)") (class "Default")
      (node (ref "J1") (pin "B2") (pinfunction "TX2+_B2") (pintype "bidirectional"))
    )
    (net (code "129") (name "unconnected-(J1-TX2--PadB3)") (class "Default")
      (node (ref "J1") (pin "B3") (pinfunction "TX2-_B3") (pintype "bidirectional"))
    )
    (net (code "130") (name "unconnected-(J2-Pad1)") (class "Default")
      (node (ref "J2") (pin "1") (pinfunction "1_1") (pintype "passive"))
    )
    (net (code "131") (name "unconnected-(J2-Pad2)") (class "Default")
      (node (ref "J2") (pin "2") (pinfunction "2_2") (pintype "passive"))
    )
    (net (code "132") (name "unconnected-(J2-Pad3)") (class "Default")
      (node (ref "J2") (pin "3") (pinfunction "3_3") (pintype "passive"))
    )
    (net (code "133") (name "unconnected-(J2-Pad4)") (class "Default")
      (node (ref "J2") (pin "4") (pinfunction "4_4") (pintype "passive"))
    )
    (net (code "134") (name "unconnected-(J2-Pad5)") (class "Default")
      (node (ref "J2") (pin "5") (pinfunction "5_5") (pintype "passive"))
    )
    (net (code "135") (name "unconnected-(J2-Pad6)") (class "Default")
      (node (ref "J2") (pin "6") (pinfunction "6_6") (pintype "passive"))
    )
    (net (code "136") (name "unconnected-(J2-Pad7)") (class "Default")
      (node (ref "J2") (pin "7") (pinfunction "7_7") (pintype "passive"))
    )
    (net (code "137") (name "unconnected-(J2-Pad8)") (class "Default")
      (node (ref "J2") (pin "8") (pinfunction "8_8") (pintype "passive"))
    )
    (net (code "138") (name "unconnected-(J2-Pad9)") (class "Default")
      (node (ref "J2") (pin "9") (pinfunction "9_9") (pintype "passive"))
    )
    (net (code "139") (name "unconnected-(J3-Pad1)") (class "Default")
      (node (ref "J3") (pin "1") (pinfunction "1_1") (pintype "passive"))
    )
    (net (code "140") (name "unconnected-(J3-Pad2)") (class "Default")
      (node (ref "J3") (pin "2") (pinfunction "2_2") (pintype "passive"))
    )
    (net (code "141") (name "unconnected-(J3-Pad3)") (class "Default")
      (node (ref "J3") (pin "3") (pinfunction "3_3") (pintype "passive"))
    )
    (net (code "142") (name "unconnected-(J3-Pad4)") (class "Default")
      (node (ref "J3") (pin "4") (pinfunction "4_4") (pintype "passive"))
    )
    (net (code "143") (name "unconnected-(J3-Pad5)") (class "Default")
      (node (ref "J3") (pin "5") (pinfunction "5_5") (pintype "passive"))
    )
    (net (code "144") (name "unconnected-(J3-Pad6)") (class "Default")
      (node (ref "J3") (pin "6") (pinfunction "6_6") (pintype "passive"))
    )
    (net (code "145") (name "unconnected-(J3-Pad7)") (class "Default")
      (node (ref "J3") (pin "7") (pinfunction "7_7") (pintype "passive"))
    )
    (net (code "146") (name "unconnected-(J3-Pad8)") (class "Default")
      (node (ref "J3") (pin "8") (pinfunction "8_8") (pintype "passive"))
    )
    (net (code "147") (name "unconnected-(J3-Pad9)") (class "Default")
      (node (ref "J3") (pin "9") (pinfunction "9_9") (pintype "passive"))
    )
    (net (code "148") (name "unconnected-(J4-Pad1)") (class "Default")
      (node (ref "J4") (pin "1") (pinfunction "1_1") (pintype "passive"))
    )
    (net (code "149") (name "unconnected-(J4-Pad2)") (class "Default")
      (node (ref "J4") (pin "2") (pinfunction "2_2") (pintype "passive"))
    )
    (net (code "150") (name "unconnected-(J4-Pad3)") (class "Default")
      (node (ref "J4") (pin "3") (pinfunction "3_3") (pintype "passive"))
    )
    (net (code "151") (name "unconnected-(J4-Pad4)") (class "Default")
      (node (ref "J4") (pin "4") (pinfunction "4_4") (pintype "passive"))
    )
    (net (code "152") (name "unconnected-(J4-Pad5)") (class "Default")
      (node (ref "J4") (pin "5") (pinfunction "5_5") (pintype "passive"))
    )
    (net (code "153") (name "unconnected-(J4-Pad6)") (class "Default")
      (node (ref "J4") (pin "6") (pinfunction "6_6") (pintype "passive"))
    )
    (net (code "154") (name "unconnected-(J4-Pad7)") (class "Default")
      (node (ref "J4") (pin "7") (pinfunction "7_7") (pintype "passive"))
    )
    (net (code "155") (name "unconnected-(J4-Pad8)") (class "Default")
      (node (ref "J4") (pin "8") (pinfunction "8_8") (pintype "passive"))
    )
    (net (code "156") (name "unconnected-(J4-Pad9)") (class "Default")
      (node (ref "J4") (pin "9") (pinfunction "9_9") (pintype "passive"))
    )
    (net (code "157") (name "unconnected-(J4-Pad10)") (class "Default")
      (node (ref "J4") (pin "10") (pinfunction "10_10") (pintype "passive"))
    )
    (net (code "158") (name "unconnected-(J4-Pad11)") (class "Default")
      (node (ref "J4") (pin "11") (pinfunction "11_11") (pintype "passive"))
    )
    (net (code "159") (name "unconnected-(J4-Pad12)") (class "Default")
      (node (ref "J4") (pin "12") (pinfunction "12_12") (pintype "passive"))
    )
    (net (code "160") (name "unconnected-(J4-Pad13)") (class "Default")
      (node (ref "J4") (pin "13") (pinfunction "13_13") (pintype "passive"))
    )
    (net (code "161") (name "unconnected-(J4-Pad14)") (class "Default")
      (node (ref "J4") (pin "14") (pinfunction "14_14") (pintype "passive"))
    )
    (net (code "162") (name "unconnected-(J4-Pad15)") (class "Default")
      (node (ref "J4") (pin "15") (pinfunction "15_15") (pintype "passive"))
    )
    (net (code "163") (name "unconnected-(J4-Pad16)") (class "Default")
      (node (ref "J4") (pin "16") (pinfunction "16_16") (pintype "passive"))
    )
    (net (code "164") (name "unconnected-(J4-Pad17)") (class "Default")
      (node (ref "J4") (pin "17") (pinfunction "17_17") (pintype "passive"))
    )
    (net (code "165") (name "unconnected-(J4-Pad18)") (class "Default")
      (node (ref "J4") (pin "18") (pinfunction "18_18") (pintype "passive"))
    )
    (net (code "166") (name "unconnected-(R15-Pad1)") (class "Default")
      (node (ref "R15") (pin "1") (pinfunction "1_1") (pintype "passive"))
    )
    (net (code "167") (name "unconnected-(R15-Pad2)") (class "Default")
      (node (ref "R15") (pin "2") (pinfunction "2_2") (pintype "passive"))
    )
    (net (code "168") (name "unconnected-(R16-Pad1)") (class "Default")
      (node (ref "R16") (pin "1") (pinfunction "1_1") (pintype "passive"))
    )
    (net (code "169") (name "unconnected-(R16-Pad2)") (class "Default")
      (node (ref "R16") (pin "2") (pinfunction "2_2") (pintype "passive"))
    )
    (net (code "170") (name "unconnected-(R17-Pad1)") (class "Default")
      (node (ref "R17") (pin "1") (pinfunction "1_1") (pintype "passive"))
    )
    (net (code "171") (name "unconnected-(R17-Pad2)") (class "Default")
      (node (ref "R17") (pin "2") (pinfunction "2_2") (pintype "passive"))
    )
    (net (code "172") (name "unconnected-(U1-CLK-Pad20)") (class "Default")
      (node (ref "U1") (pin "20") (pinfunction "CLK_20") (pintype "bidirectional"))
    )
    (net (code "173") (name "unconnected-(U1-CMD-Pad19)") (class "Default")
      (node (ref "U1") (pin "19") (pinfunction "CMD_19") (pintype "bidirectional"))
    )
    (net (code "174") (name "unconnected-(U1-IO2-Pad24)") (class "Default")
      (node (ref "U1") (pin "24") (pinfunction "IO2_24") (pintype "bidirectional"))
    )
    (net (code "175") (name "unconnected-(U1-IO4-Pad26)") (class "Default")
      (node (ref "U1") (pin "26") (pinfunction "IO4_26") (pintype "bidirectional"))
    )
    (net (code "176") (name "unconnected-(U1-IO12-Pad14)") (class "Default")
      (node (ref "U1") (pin "14") (pinfunction "IO12_14") (pintype "bidirectional"))
    )
    (net (code "177") (name "unconnected-(U1-IO13-Pad16)") (class "Default")
      (node (ref "U1") (pin "16") (pinfunction "IO13_16") (pintype "bidirectional"))
    )
    (net (code "178") (name "unconnected-(U1-IO15-Pad23)") (class "Default")
      (node (ref "U1") (pin "23") (pinfunction "IO15_23") (pintype "bidirectional"))
    )
    (net (code "179") (name "unconnected-(U1-IO16-Pad27)") (class "Default")
      (node (ref "U1") (pin "27") (pinfunction "IO16_27") (pintype "bidirectional"))
    )
    (net (code "180") (name "unconnected-(U1-IO17-Pad28)") (class "Default")
      (node (ref "U1") (pin "28") (pinfunction "IO17_28") (pintype "bidirectional"))
    )
    (net (code "181") (name "unconnected-(U1-IO19-Pad31)") (class "Default")
      (node (ref "U1") (pin "31") (pinfunction "IO19_31") (pintype "bidirectional"))
    )
    (net (code "182") (name "unconnected-(U1-IO32-Pad8)") (class "Default")
      (node (ref "U1") (pin "8") (pinfunction "IO32_8") (pintype "bidirectional"))
    )
    (net (code "183") (name "unconnected-(U1-IO34-Pad6)") (class "Default")
      (node (ref "U1") (pin "6") (pinfunction "IO34_6") (pintype "bidirectional"))
    )
    (net (code "184") (name "unconnected-(U1-IO35-Pad7)") (class "Default")
      (node (ref "U1") (pin "7") (pinfunction "IO35_7") (pintype "bidirectional"))
    )
    (net (code "185") (name "unconnected-(U1-SD0-Pad21)") (class "Default")
      (node (ref "U1") (pin "21") (pinfunction "SD0_21") (pintype "bidirectional"))
    )
    (net (code "186") (name "unconnected-(U1-SD1-Pad22)") (class "Default")
      (node (ref "U1") (pin "22") (pinfunction "SD1_22") (pintype "bidirectional"))
    )
    (net (code "187") (name "unconnected-(U1-SD2-Pad17)") (class "Default")
      (node (ref "U1") (pin "17") (pinfunction "SD2_17") (pintype "bidirectional"))
    )
    (net (code "188") (name "unconnected-(U1-SD3-Pad18)") (class "Default")
      (node (ref "U1") (pin "18") (pinfunction "SD3_18") (pintype "bidirectional"))
    )
    (net (code "189") (name "unconnected-(U1-SVN-Pad5)") (class "Default")
      (node (ref "U1") (pin "5") (pinfunction "SVN_5") (pintype "bidirectional"))
    )
    (net (code "190") (name "unconnected-(U1-SVP-Pad4)") (class "Default")
      (node (ref "U1") (pin "4") (pinfunction "SVP_4") (pintype "bidirectional"))
    )
    (net (code "191") (name "unconnected-(U2A-PA02-Pad1)") (class "Default")
      (node (ref "U2") (pin "1") (pinfunction "PA02_1") (pintype "bidirectional"))
    )
    (net (code "192") (name "unconnected-(U2A-PA03-Pad2)") (class "Default")
      (node (ref "U2") (pin "2") (pinfunction "PA03_2") (pintype "bidirectional"))
    )
    (net (code "193") (name "unconnected-(U2A-PA04-Pad3)") (class "Default")
      (node (ref "U2") (pin "3") (pinfunction "PA04_3") (pintype "bidirectional"))
    )
    (net (code "194") (name "unconnected-(U2A-PA05-Pad4)") (class "Default")
      (node (ref "U2") (pin "4") (pinfunction "PA05_4") (pintype "bidirectional"))
    )
    (net (code "195") (name "unconnected-(U2A-PA06-Pad5)") (class "Default")
      (node (ref "U2") (pin "5") (pinfunction "PA06_5") (pintype "bidirectional"))
    )
    (net (code "196") (name "unconnected-(U2A-PA07-Pad6)") (class "Default")
      (node (ref "U2") (pin "6") (pinfunction "PA07_6") (pintype "bidirectional"))
    )
    (net (code "197") (name "unconnected-(U2A-PA08{slash}XIN32-Pad7)") (class "Default")
      (node (ref "U2") (pin "7") (pinfunction "PA08/XIN32_7") (pintype "bidirectional"))
    )
    (net (code "198") (name "unconnected-(U2A-PA09{slash}XOUT32-Pad8)") (class "Default")
      (node (ref "U2") (pin "8") (pinfunction "PA09/XOUT32_8") (pintype "bidirectional"))
    )
    (net (code "199") (name "unconnected-(U2A-PA10-Pad9)") (class "Default")
      (node (ref "U2") (pin "9") (pinfunction "PA10_9") (pintype "bidirectional"))
    )
    (net (code "200") (name "unconnected-(U2A-PA11-Pad10)") (class "Default")
      (node (ref "U2") (pin "10") (pinfunction "PA11_10") (pintype "bidirectional"))
    )
    (net (code "201") (name "unconnected-(U2A-PA16-Pad13)") (class "Default")
      (node (ref "U2") (pin "13") (pinfunction "PA16_13") (pintype "bidirectional"))
    )
    (net (code "202") (name "unconnected-(U2A-PA17-Pad14)") (class "Default")
      (node (ref "U2") (pin "14") (pinfunction "PA17_14") (pintype "bidirectional"))
    )
    (net (code "203") (name "unconnected-(U2A-PA27-Pad17)") (class "Default")
      (node (ref "U2") (pin "17") (pinfunction "PA27_17") (pintype "bidirectional"))
    )
    (net (code "204") (name "unconnected-(U6-1A-Pad3)") (class "Default")
      (node (ref "U6") (pin "3") (pinfunction "1A_3") (pintype "bidirectional"))
    )
    (net (code "205") (name "unconnected-(U6-1Y-Pad2)") (class "Default")
      (node (ref "U6") (pin "2") (pinfunction "1Y_2") (pintype "bidirectional"))
    )
    (net (code "206") (name "unconnected-(U6-4A-Pad9)") (class "Default")
      (node (ref "U6") (pin "9") (pinfunction "4A_9") (pintype "bidirectional"))
    )
    (net (code "207") (name "unconnected-(U6-4Y-Pad10)") (class "Default")
      (node (ref "U6") (pin "10") (pinfunction "4Y_10") (pintype "bidirectional"))
    )
    (net (code "208") (name "unconnected-(XTAL1-Pad1)") (class "Default")
      (node (ref "XTAL1") (pin "1") (pinfunction "1_1") (pintype "passive"))
    )
    (net (code "209") (name "unconnected-(XTAL1-Pad2)") (class "Default")
      (node (ref "XTAL1") (pin "2") (pinfunction "2_2") (pintype "passive"))
    )
  )
)
